# M9-PowerMeas.net
KiCad netlist of a schematic drawn in Altium Designer
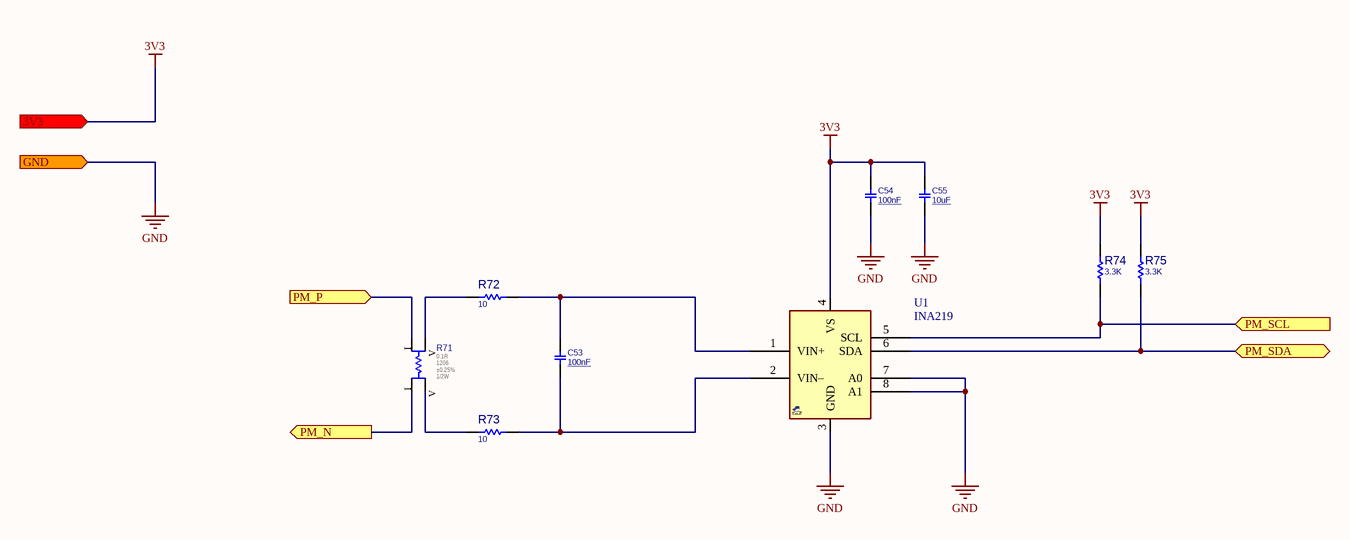
[diagram p0: M9-PowerMeas.SchDoc]

(export (version "E")
  (design (tool "Eeschema 10.0.6"))
  (components
    (comp (ref "C53")
      (value "100nF")
      (footprint "C1206")
      (description "CAP, MLCC, 1nF, 50V, C0G, 10%, 0402")
      (fields (field (name "MANF_P#") "MANF_PART#") (field (name "MANF") "Murata"))
      (libsource (lib "passive_smd") (part "CAP_SMD_MLCC"))
    )
    (comp (ref "C54")
      (value "100nF")
      (footprint "C1206")
      (description "CAP, MLCC, 1nF, 50V, C0G, 10%, 0402")
      (fields (field (name "MANF_P#") "MANF_PART#") (field (name "MANF") "Murata"))
      (libsource (lib "passive_smd") (part "CAP_SMD_MLCC"))
    )
    (comp (ref "C55")
      (value "10uF")
      (footprint "C1206")
      (description "CAP, MLCC, 1nF, 50V, C0G, 10%, 0402")
      (fields (field (name "MANF_P#") "MANF_PART#") (field (name "MANF") "Murata"))
      (libsource (lib "passive_smd") (part "CAP_SMD_MLCC"))
    )
    (comp (ref "R71")
      (value "0.1R")
      (footprint "R-1206_LVK:R-1206_LVK")
      (description "Resistor,S,TF,0.1R,1/2W,0.25%,1206")
      (fields
        (field (name "PACKAGE/CASE") "1206")
        (field (name "TOLERANCE") "±0.25%")
        (field (name "POWER") "1/2W")
      )
      (libsource (lib "Crouse") (part "Res_LVK"))
    )
    (comp (ref "R72")
      (value "10")
      (footprint "R1206")
      (description "RESISTOR, SMD")
      (libsource (lib "passive_smd") (part "RES_SMD"))
    )
    (comp (ref "R73")
      (value "10")
      (footprint "R1206")
      (description "RESISTOR, SMD")
      (libsource (lib "passive_smd") (part "RES_SMD"))
    )
    (comp (ref "R74")
      (value "3.3K")
      (footprint "R1206")
      (description "RESISTOR, SMD")
      (libsource (lib "passive_smd") (part "RES_SMD"))
    )
    (comp (ref "R75")
      (value "3.3K")
      (footprint "R1206")
      (description "RESISTOR, SMD")
      (libsource (lib "passive_smd") (part "RES_SMD"))
    )
    (comp (ref "U1")
      (value "INA219")
      (footprint "SOT23_8")
      (description "Current/Power Monitor, Zerø-Drift, Bidirectional, I2C")
      (fields (field (name "MANF") "TEXAS INSTRUMENTS") (field (name "MANF_P#") "INA219AIDCN, INA219BIDCN"))
      (libsource (lib "amp_instrument") (part "INA219_SOT23"))
    )
  )
  (nets
    (net (code "1") (name "/PM_N") (class "Default")
      (node (ref "R71") (pin "2") (pinfunction "I_2") (pintype "passive"))
    )
    (net (code "2") (name "/PM_P") (class "Default")
      (node (ref "R71") (pin "4") (pinfunction "I_4") (pintype "passive"))
    )
    (net (code "3") (name "/PM_SCL") (class "Default")
      (node (ref "R74") (pin "1") (pinfunction "1_1") (pintype "passive"))
      (node (ref "U1") (pin "5") (pinfunction "SCL_5") (pintype "passive"))
    )
    (net (code "4") (name "/PM_SDA") (class "Default")
      (node (ref "R75") (pin "1") (pinfunction "1_1") (pintype "passive"))
      (node (ref "U1") (pin "6") (pinfunction "SDA_6") (pintype "passive"))
    )
    (net (code "5") (name "3V3") (class "Default")
      (node (ref "C54") (pin "2") (pinfunction "2_2") (pintype "passive"))
      (node (ref "C55") (pin "2") (pinfunction "2_2") (pintype "passive"))
      (node (ref "R74") (pin "2") (pinfunction "2_2") (pintype "passive"))
      (node (ref "R75") (pin "2") (pinfunction "2_2") (pintype "passive"))
      (node (ref "U1") (pin "4") (pinfunction "VS_4") (pintype "passive"))
    )
    (net (code "6") (name "GND") (class "Default")
      (node (ref "C54") (pin "1") (pinfunction "1_1") (pintype "passive"))
      (node (ref "C55") (pin "1") (pinfunction "1_1") (pintype "passive"))
      (node (ref "U1") (pin "3") (pinfunction "GND_3") (pintype "passive"))
      (node (ref "U1") (pin "7") (pinfunction "A0_7") (pintype "passive"))
      (node (ref "U1") (pin "8") (pinfunction "A1_8") (pintype "passive"))
    )
    (net (code "7") (name "Net-(R71-V-Pad1)") (class "Default")
      (node (ref "R71") (pin "1") (pinfunction "V_1") (pintype "passive"))
      (node (ref "R73") (pin "2") (pinfunction "2_2") (pintype "passive"))
    )
    (net (code "8") (name "Net-(R71-V-Pad3)") (class "Default")
      (node (ref "R71") (pin "3") (pinfunction "V_3") (pintype "passive"))
      (node (ref "R72") (pin "2") (pinfunction "2_2") (pintype "passive"))
    )
    (net (code "9") (name "Net-(U1-VIN+)") (class "Default")
      (node (ref "C53") (pin "2") (pinfunction "2_2") (pintype "passive"))
      (node (ref "R72") (pin "1") (pinfunction "1_1") (pintype "passive"))
      (node (ref "U1") (pin "1") (pinfunction "VIN+_1") (pintype "passive"))
    )
    (net (code "10") (name "Net-(U1-VIN–)") (class "Default")
      (node (ref "C53") (pin "1") (pinfunction "1_1") (pintype "passive"))
      (node (ref "R73") (pin "1") (pinfunction "1_1") (pintype "passive"))
      (node (ref "U1") (pin "2") (pinfunction "VIN–_2") (pintype "passive"))
    )
  )
)
